# 8mixer.net
KiCad netlist of a schematic drawn in EAGLE
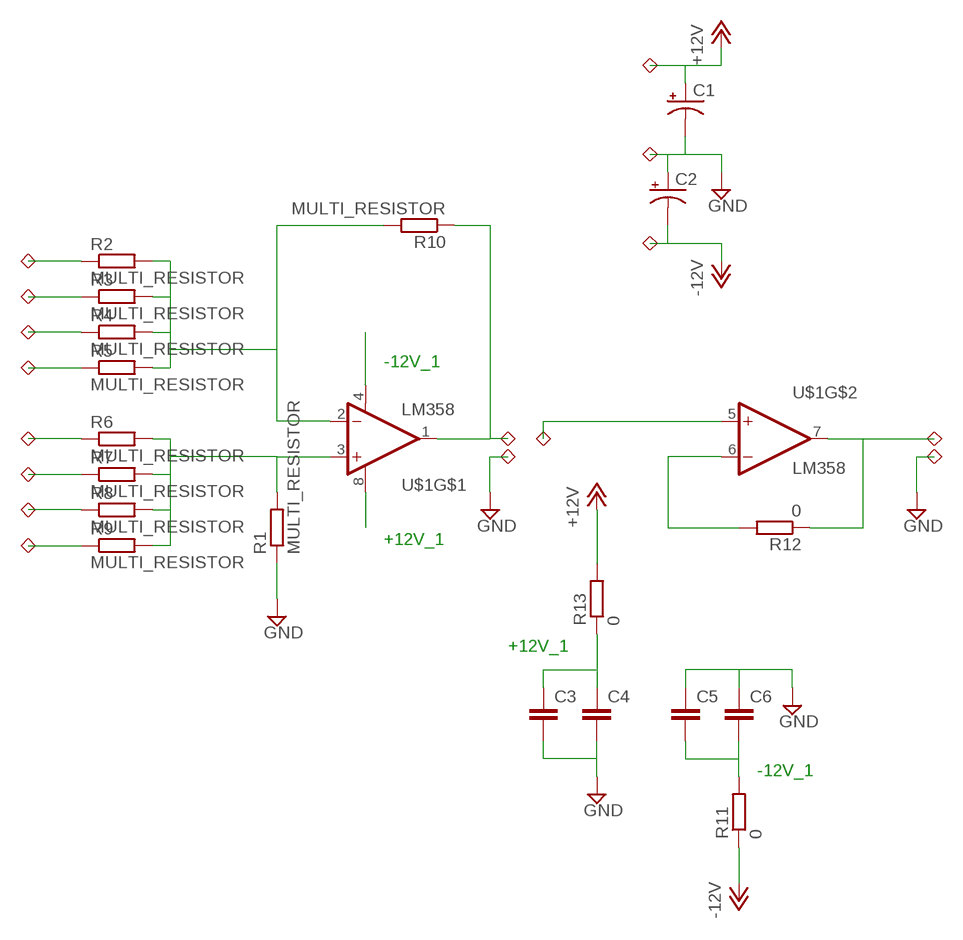
[diagram p0: schematic, sheet 1]

(export (version "E")
  (design (tool "Eeschema 10.0.6"))
  (components
    (comp (ref "C1")
      (value "CPOL-USSMCE")
      (footprint "eagle-import:SMC_E")
      (libsource (lib "eagle-import") (part "CPOL-USSMCE"))
    )
    (comp (ref "C2")
      (value "CPOL-USSMCE")
      (footprint "eagle-import:SMC_E")
      (libsource (lib "eagle-import") (part "CPOL-USSMCE"))
    )
    (comp (ref "C3")
      (value "C-EUC0805")
      (footprint "eagle-import:C0805")
      (libsource (lib "eagle-import") (part "C-EUC0805"))
    )
    (comp (ref "C4")
      (value "C-EUC0805")
      (footprint "eagle-import:C0805")
      (libsource (lib "eagle-import") (part "C-EUC0805"))
    )
    (comp (ref "C5")
      (value "C-EUC0805")
      (footprint "eagle-import:C0805")
      (libsource (lib "eagle-import") (part "C-EUC0805"))
    )
    (comp (ref "C6")
      (value "C-EUC0805")
      (footprint "eagle-import:C0805")
      (libsource (lib "eagle-import") (part "C-EUC0805"))
    )
    (comp (ref "R1")
      (value "MULTI_RESISTOR")
      (footprint "eagle-import:MULTI_PAD")
      (libsource (lib "eagle-import") (part "MULTI_RESISTOR"))
    )
    (comp (ref "R2")
      (value "MULTI_RESISTOR")
      (footprint "eagle-import:MULTI_PAD")
      (libsource (lib "eagle-import") (part "MULTI_RESISTOR"))
    )
    (comp (ref "R3")
      (value "MULTI_RESISTOR")
      (footprint "eagle-import:MULTI_PAD")
      (libsource (lib "eagle-import") (part "MULTI_RESISTOR"))
    )
    (comp (ref "R4")
      (value "MULTI_RESISTOR")
      (footprint "eagle-import:MULTI_PAD")
      (libsource (lib "eagle-import") (part "MULTI_RESISTOR"))
    )
    (comp (ref "R5")
      (value "MULTI_RESISTOR")
      (footprint "eagle-import:MULTI_PAD")
      (libsource (lib "eagle-import") (part "MULTI_RESISTOR"))
    )
    (comp (ref "R6")
      (value "MULTI_RESISTOR")
      (footprint "eagle-import:MULTI_PAD")
      (libsource (lib "eagle-import") (part "MULTI_RESISTOR"))
    )
    (comp (ref "R7")
      (value "MULTI_RESISTOR")
      (footprint "eagle-import:MULTI_PAD")
      (libsource (lib "eagle-import") (part "MULTI_RESISTOR"))
    )
    (comp (ref "R8")
      (value "MULTI_RESISTOR")
      (footprint "eagle-import:MULTI_PAD")
      (libsource (lib "eagle-import") (part "MULTI_RESISTOR"))
    )
    (comp (ref "R9")
      (value "MULTI_RESISTOR")
      (footprint "eagle-import:MULTI_PAD")
      (libsource (lib "eagle-import") (part "MULTI_RESISTOR"))
    )
    (comp (ref "R10")
      (value "MULTI_RESISTOR")
      (footprint "eagle-import:MULTI_PAD")
      (libsource (lib "eagle-import") (part "MULTI_RESISTOR"))
    )
    (comp (ref "R11")
      (value "0")
      (footprint "eagle-import:M1206")
      (libsource (lib "eagle-import") (part "R-EU_M1206"))
    )
    (comp (ref "R12")
      (value "0")
      (footprint "eagle-import:M1206")
      (libsource (lib "eagle-import") (part "R-EU_M1206"))
    )
    (comp (ref "R13")
      (value "0")
      (footprint "eagle-import:M1206")
      (libsource (lib "eagle-import") (part "R-EU_M1206"))
    )
    (comp (ref "U$1")
      (value "LM358")
      (footprint "eagle-import:SO08")
      (libsource (lib "eagle-import") (part "LM358"))
    )
    (comp (ref "U$2")
      (value "1PIN")
      (footprint "eagle-import:THUMBNAIL")
      (libsource (lib "eagle-import") (part "1PIN"))
    )
    (comp (ref "U$3")
      (value "1PIN")
      (footprint "eagle-import:THUMBNAIL")
      (libsource (lib "eagle-import") (part "1PIN"))
    )
    (comp (ref "U$4")
      (value "1PIN")
      (footprint "eagle-import:THUMBNAIL")
      (libsource (lib "eagle-import") (part "1PIN"))
    )
    (comp (ref "U$5")
      (value "1PIN")
      (footprint "eagle-import:THUMBNAIL")
      (libsource (lib "eagle-import") (part "1PIN"))
    )
    (comp (ref "U$6")
      (value "1PIN")
      (footprint "eagle-import:THUMBNAIL")
      (libsource (lib "eagle-import") (part "1PIN"))
    )
    (comp (ref "U$7")
      (value "1PIN")
      (footprint "eagle-import:THUMBNAIL")
      (libsource (lib "eagle-import") (part "1PIN"))
    )
    (comp (ref "U$8")
      (value "1PIN")
      (footprint "eagle-import:THUMBNAIL")
      (libsource (lib "eagle-import") (part "1PIN"))
    )
    (comp (ref "U$9")
      (value "1PIN")
      (footprint "eagle-import:THUMBNAIL")
      (libsource (lib "eagle-import") (part "1PIN"))
    )
    (comp (ref "U$10")
      (value "1PIN")
      (footprint "eagle-import:THUMBNAIL")
      (libsource (lib "eagle-import") (part "1PIN"))
    )
    (comp (ref "U$11")
      (value "1PIN")
      (footprint "eagle-import:THUMBNAIL")
      (libsource (lib "eagle-import") (part "1PIN"))
    )
    (comp (ref "U$12")
      (value "1PIN")
      (footprint "eagle-import:THUMBNAIL")
      (libsource (lib "eagle-import") (part "1PIN"))
    )
    (comp (ref "U$13")
      (value "1PIN")
      (footprint "eagle-import:THUMBNAIL")
      (libsource (lib "eagle-import") (part "1PIN"))
    )
    (comp (ref "U$14")
      (value "1PIN")
      (footprint "eagle-import:THUMBNAIL")
      (libsource (lib "eagle-import") (part "1PIN"))
    )
    (comp (ref "U$15")
      (value "1PIN")
      (footprint "eagle-import:THUMBNAIL")
      (libsource (lib "eagle-import") (part "1PIN"))
    )
    (comp (ref "U$16")
      (value "1PIN")
      (footprint "eagle-import:THUMBNAIL")
      (libsource (lib "eagle-import") (part "1PIN"))
    )
    (comp (ref "U$17")
      (value "1PIN")
      (footprint "eagle-import:THUMBNAIL")
      (libsource (lib "eagle-import") (part "1PIN"))
    )
  )
  (nets
    (net (code "1") (name "+12V") (class "Default")
      (node (ref "C1") (pin "+") (pinfunction "+_+") (pintype "passive"))
      (node (ref "R13") (pin "2") (pinfunction "2_2") (pintype "passive"))
      (node (ref "U$10") (pin "P$1") (pinfunction "P$1_P$1") (pintype "bidirectional"))
    )
    (net (code "2") (name "-12V") (class "Default")
      (node (ref "C2") (pin "-") (pinfunction "-_-") (pintype "passive"))
      (node (ref "R11") (pin "1") (pinfunction "1_1") (pintype "passive"))
      (node (ref "U$12") (pin "P$1") (pinfunction "P$1_P$1") (pintype "bidirectional"))
    )
    (net (code "3") (name "/+12V_1") (class "Default")
      (node (ref "C3") (pin "1") (pinfunction "1_1") (pintype "passive"))
      (node (ref "C4") (pin "1") (pinfunction "1_1") (pintype "passive"))
      (node (ref "R13") (pin "1") (pinfunction "1_1") (pintype "passive"))
      (node (ref "U$1") (pin "8") (pinfunction "V+_8") (pintype "power_in"))
    )
    (net (code "4") (name "/-12V_1") (class "Default")
      (node (ref "C5") (pin "2") (pinfunction "2_2") (pintype "passive"))
      (node (ref "C6") (pin "2") (pinfunction "2_2") (pintype "passive"))
      (node (ref "R11") (pin "2") (pinfunction "2_2") (pintype "passive"))
      (node (ref "U$1") (pin "4") (pinfunction "V-_4") (pintype "power_in"))
    )
    (net (code "5") (name "GND") (class "Default")
      (node (ref "C1") (pin "-") (pinfunction "-_-") (pintype "passive"))
      (node (ref "C2") (pin "+") (pinfunction "+_+") (pintype "passive"))
      (node (ref "C3") (pin "2") (pinfunction "2_2") (pintype "passive"))
      (node (ref "C4") (pin "2") (pinfunction "2_2") (pintype "passive"))
      (node (ref "C5") (pin "1") (pinfunction "1_1") (pintype "passive"))
      (node (ref "C6") (pin "1") (pinfunction "1_1") (pintype "passive"))
      (node (ref "R1") (pin "1") (pinfunction "1_1") (pintype "passive"))
      (node (ref "U$11") (pin "P$1") (pinfunction "P$1_P$1") (pintype "bidirectional"))
      (node (ref "U$14") (pin "P$1") (pinfunction "P$1_P$1") (pintype "bidirectional"))
      (node (ref "U$16") (pin "P$1") (pinfunction "P$1_P$1") (pintype "bidirectional"))
    )
    (net (code "6") (name "Net-(R2-Pad1)") (class "Default")
      (node (ref "R2") (pin "1") (pinfunction "1_1") (pintype "passive"))
      (node (ref "U$2") (pin "P$1") (pinfunction "P$1_P$1") (pintype "bidirectional"))
    )
    (net (code "7") (name "Net-(R3-Pad1)") (class "Default")
      (node (ref "R3") (pin "1") (pinfunction "1_1") (pintype "passive"))
      (node (ref "U$3") (pin "P$1") (pinfunction "P$1_P$1") (pintype "bidirectional"))
    )
    (net (code "8") (name "Net-(R4-Pad1)") (class "Default")
      (node (ref "R4") (pin "1") (pinfunction "1_1") (pintype "passive"))
      (node (ref "U$4") (pin "P$1") (pinfunction "P$1_P$1") (pintype "bidirectional"))
    )
    (net (code "9") (name "Net-(R5-Pad1)") (class "Default")
      (node (ref "R5") (pin "1") (pinfunction "1_1") (pintype "passive"))
      (node (ref "U$5") (pin "P$1") (pinfunction "P$1_P$1") (pintype "bidirectional"))
    )
    (net (code "10") (name "Net-(R6-Pad1)") (class "Default")
      (node (ref "R6") (pin "1") (pinfunction "1_1") (pintype "passive"))
      (node (ref "U$6") (pin "P$1") (pinfunction "P$1_P$1") (pintype "bidirectional"))
    )
    (net (code "11") (name "Net-(R7-Pad1)") (class "Default")
      (node (ref "R7") (pin "1") (pinfunction "1_1") (pintype "passive"))
      (node (ref "U$7") (pin "P$1") (pinfunction "P$1_P$1") (pintype "bidirectional"))
    )
    (net (code "12") (name "Net-(R8-Pad1)") (class "Default")
      (node (ref "R8") (pin "1") (pinfunction "1_1") (pintype "passive"))
      (node (ref "U$8") (pin "P$1") (pinfunction "P$1_P$1") (pintype "bidirectional"))
    )
    (net (code "13") (name "Net-(R9-Pad1)") (class "Default")
      (node (ref "R9") (pin "1") (pinfunction "1_1") (pintype "passive"))
      (node (ref "U$9") (pin "P$1") (pinfunction "P$1_P$1") (pintype "bidirectional"))
    )
    (net (code "14") (name "Net-(U$1A-+IN)") (class "Default")
      (node (ref "R1") (pin "2") (pinfunction "2_2") (pintype "passive"))
      (node (ref "R6") (pin "2") (pinfunction "2_2") (pintype "passive"))
      (node (ref "R7") (pin "2") (pinfunction "2_2") (pintype "passive"))
      (node (ref "R8") (pin "2") (pinfunction "2_2") (pintype "passive"))
      (node (ref "R9") (pin "2") (pinfunction "2_2") (pintype "passive"))
      (node (ref "U$1") (pin "3") (pinfunction "+IN_3") (pintype "input"))
    )
    (net (code "15") (name "Net-(U$1A--IN)") (class "Default")
      (node (ref "R10") (pin "2") (pinfunction "2_2") (pintype "passive"))
      (node (ref "R2") (pin "2") (pinfunction "2_2") (pintype "passive"))
      (node (ref "R3") (pin "2") (pinfunction "2_2") (pintype "passive"))
      (node (ref "R4") (pin "2") (pinfunction "2_2") (pintype "passive"))
      (node (ref "R5") (pin "2") (pinfunction "2_2") (pintype "passive"))
      (node (ref "U$1") (pin "2") (pinfunction "-IN_2") (pintype "input"))
    )
    (net (code "16") (name "Net-(U$1A-OUT)") (class "Default")
      (node (ref "R10") (pin "1") (pinfunction "1_1") (pintype "passive"))
      (node (ref "U$1") (pin "1") (pinfunction "OUT_1") (pintype "output"))
      (node (ref "U$13") (pin "P$1") (pinfunction "P$1_P$1") (pintype "bidirectional"))
    )
    (net (code "17") (name "Net-(U$1B-+IN)") (class "Default")
      (node (ref "U$1") (pin "5") (pinfunction "+IN_5") (pintype "input"))
      (node (ref "U$17") (pin "P$1") (pinfunction "P$1_P$1") (pintype "bidirectional"))
    )
    (net (code "18") (name "Net-(U$1B--IN)") (class "Default")
      (node (ref "R12") (pin "2") (pinfunction "2_2") (pintype "passive"))
      (node (ref "U$1") (pin "6") (pinfunction "-IN_6") (pintype "input"))
    )
    (net (code "19") (name "Net-(U$1B-OUT)") (class "Default")
      (node (ref "R12") (pin "1") (pinfunction "1_1") (pintype "passive"))
      (node (ref "U$1") (pin "7") (pinfunction "OUT_7") (pintype "output"))
      (node (ref "U$15") (pin "P$1") (pinfunction "P$1_P$1") (pintype "bidirectional"))
    )
  )
)
